# RevA.net
KiCad netlist of a schematic drawn in EAGLE
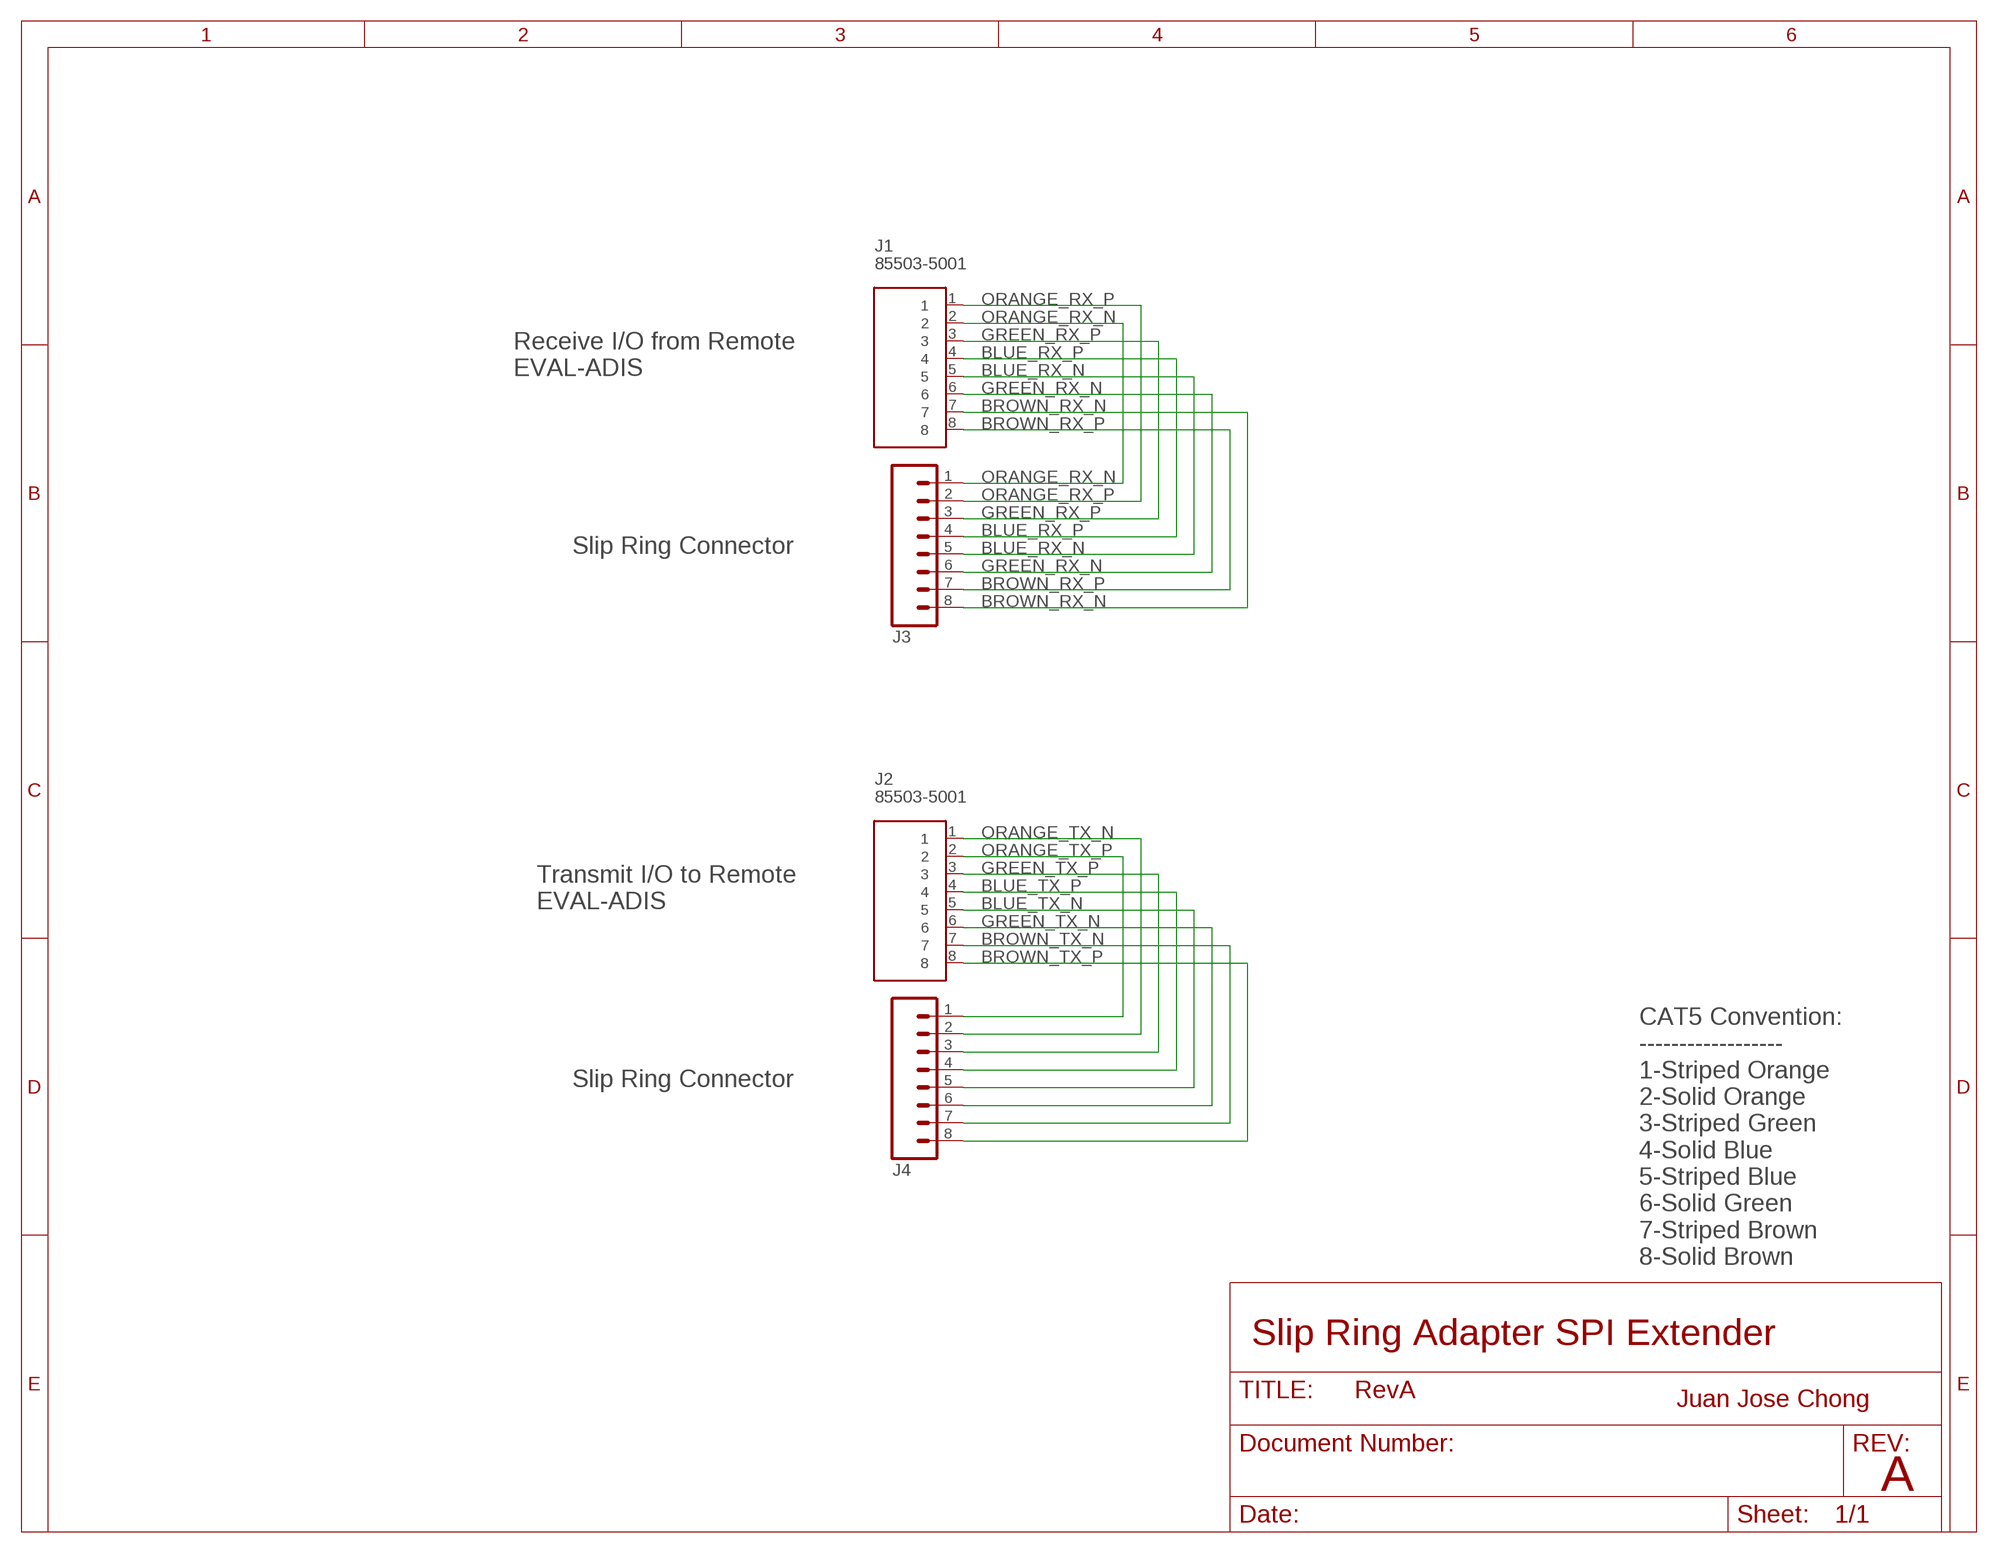
[diagram p0: schematic, sheet 1]

(export (version "E")
  (design (tool "Eeschema 10.0.6"))
  (components
    (comp (ref "J1")
      (value "85503-5001")
      (footprint "eagle-import:85503-5001")
      (fields (field (name "PARTNO") "855035001"))
      (libsource (lib "eagle-import") (part "85503-5001"))
    )
    (comp (ref "J2")
      (value "85503-5001")
      (footprint "eagle-import:85503-5001")
      (fields (field (name "PARTNO") "855035001"))
      (libsource (lib "eagle-import") (part "85503-5001"))
    )
    (comp (ref "J3")
      (value "M08LOCK")
      (footprint "eagle-import:1X08_LOCK")
      (libsource (lib "eagle-import") (part "M08LOCK"))
    )
    (comp (ref "J4")
      (value "M08LOCK")
      (footprint "eagle-import:1X08_LOCK")
      (libsource (lib "eagle-import") (part "M08LOCK"))
    )
  )
  (nets
    (net (code "1") (name "/BLUE_RX_N") (class "Default")
      (node (ref "J1") (pin "5") (pinfunction "5_5") (pintype "bidirectional"))
      (node (ref "J3") (pin "5") (pinfunction "5_5") (pintype "passive"))
    )
    (net (code "2") (name "/BLUE_RX_P") (class "Default")
      (node (ref "J1") (pin "4") (pinfunction "4_4") (pintype "bidirectional"))
      (node (ref "J3") (pin "4") (pinfunction "4_4") (pintype "passive"))
    )
    (net (code "3") (name "/BLUE_TX_N") (class "Default")
      (node (ref "J2") (pin "5") (pinfunction "5_5") (pintype "bidirectional"))
      (node (ref "J4") (pin "5") (pinfunction "5_5") (pintype "passive"))
    )
    (net (code "4") (name "/BLUE_TX_P") (class "Default")
      (node (ref "J2") (pin "4") (pinfunction "4_4") (pintype "bidirectional"))
      (node (ref "J4") (pin "4") (pinfunction "4_4") (pintype "passive"))
    )
    (net (code "5") (name "/BROWN_RX_N") (class "Default")
      (node (ref "J1") (pin "7") (pinfunction "7_7") (pintype "bidirectional"))
      (node (ref "J3") (pin "8") (pinfunction "8_8") (pintype "passive"))
    )
    (net (code "6") (name "/BROWN_RX_P") (class "Default")
      (node (ref "J1") (pin "8") (pinfunction "8_8") (pintype "bidirectional"))
      (node (ref "J3") (pin "7") (pinfunction "7_7") (pintype "passive"))
    )
    (net (code "7") (name "/BROWN_TX_N") (class "Default")
      (node (ref "J2") (pin "7") (pinfunction "7_7") (pintype "bidirectional"))
      (node (ref "J4") (pin "7") (pinfunction "7_7") (pintype "passive"))
    )
    (net (code "8") (name "/BROWN_TX_P") (class "Default")
      (node (ref "J2") (pin "8") (pinfunction "8_8") (pintype "bidirectional"))
      (node (ref "J4") (pin "8") (pinfunction "8_8") (pintype "passive"))
    )
    (net (code "9") (name "/GREEN_RX_N") (class "Default")
      (node (ref "J1") (pin "6") (pinfunction "6_6") (pintype "bidirectional"))
      (node (ref "J3") (pin "6") (pinfunction "6_6") (pintype "passive"))
    )
    (net (code "10") (name "/GREEN_RX_P") (class "Default")
      (node (ref "J1") (pin "3") (pinfunction "3_3") (pintype "bidirectional"))
      (node (ref "J3") (pin "3") (pinfunction "3_3") (pintype "passive"))
    )
    (net (code "11") (name "/GREEN_TX_N") (class "Default")
      (node (ref "J2") (pin "6") (pinfunction "6_6") (pintype "bidirectional"))
      (node (ref "J4") (pin "6") (pinfunction "6_6") (pintype "passive"))
    )
    (net (code "12") (name "/GREEN_TX_P") (class "Default")
      (node (ref "J2") (pin "3") (pinfunction "3_3") (pintype "bidirectional"))
      (node (ref "J4") (pin "3") (pinfunction "3_3") (pintype "passive"))
    )
    (net (code "13") (name "/ORANGE_RX_N") (class "Default")
      (node (ref "J1") (pin "2") (pinfunction "2_2") (pintype "bidirectional"))
      (node (ref "J3") (pin "1") (pinfunction "1_1") (pintype "passive"))
    )
    (net (code "14") (name "/ORANGE_RX_P") (class "Default")
      (node (ref "J1") (pin "1") (pinfunction "1_1") (pintype "bidirectional"))
      (node (ref "J3") (pin "2") (pinfunction "2_2") (pintype "passive"))
    )
    (net (code "15") (name "/ORANGE_TX_N") (class "Default")
      (node (ref "J2") (pin "1") (pinfunction "1_1") (pintype "bidirectional"))
      (node (ref "J4") (pin "2") (pinfunction "2_2") (pintype "passive"))
    )
    (net (code "16") (name "/ORANGE_TX_P") (class "Default")
      (node (ref "J2") (pin "2") (pinfunction "2_2") (pintype "bidirectional"))
      (node (ref "J4") (pin "1") (pinfunction "1_1") (pintype "passive"))
    )
  )
)
